# BMS_Carrier_-_Battery_Relay_Controls.net
KiCad netlist of a schematic drawn in Altium Designer
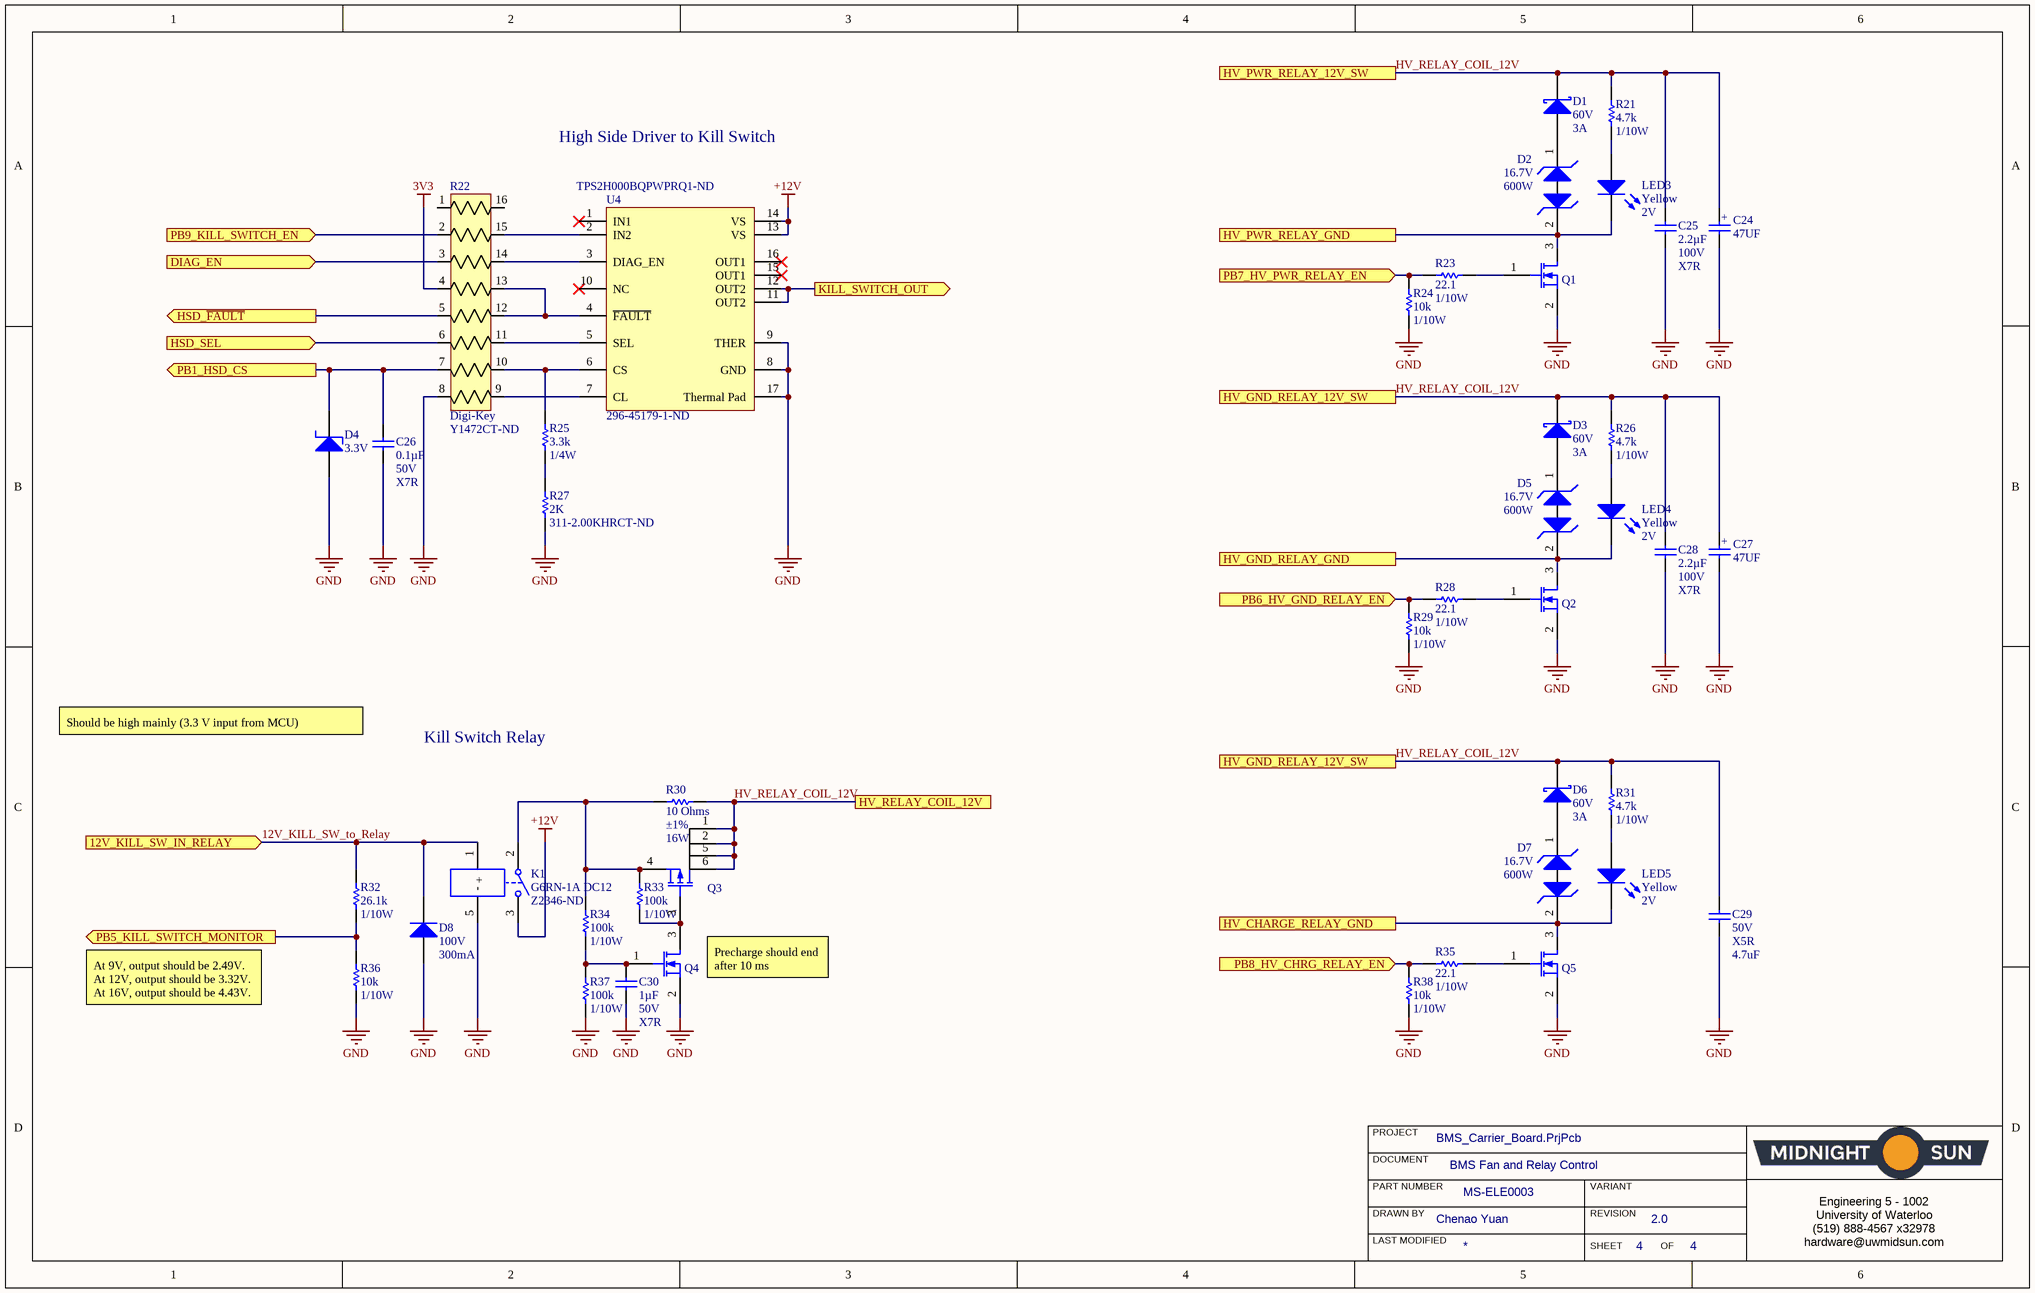
[diagram p0: BMS Carrier - Battery Relay Controls.SchDoc]

(export (version "E")
  (design (tool "Eeschema 10.0.6"))
  (components
    (comp (ref "C24")
      (value "47UF")
      (footprint "CAP ALUM 6.3MM RADIAL SMD")
      (description "47µF 35V Aluminum Electrolytic Capacitors Radial, Can - SMD 1000 Hrs @ 85°C")
      (fields (field (name "TOLERANCE") "20%") (field (name "MANUFACTURER") "Panasonic"))
      (libsource (lib "Schematic Diagrams") (part "CAP ALUM 47UF 20% 35V SMD"))
    )
    (comp (ref "C25")
      (value "CAP CER 2.2UF 100V ±20% X7R 1206")
      (footprint "CAP, 1206")
      (description "2.2µF ±20% 100V Ceramic Capacitor X7R 1206 (3216 Metric)")
      (fields
        (field (name "TOLERANCE") "±20%")
        (field (name "CAPACITANCE") "2.2µF")
        (field (name "VOLTAGE") "100V")
        (field (name "TEMPERATURE COEFFICIENT") "X7R")
      )
      (libsource (lib "Schematic Diagrams") (part "CAP CER 2.2UF 100V ±20% X7R 1206"))
    )
    (comp (ref "C26")
      (value "CAP CER 0.1UF 50V 10% X7R 0603")
      (footprint "CAP, 0603")
      (description "0.10µF ±10% 50V Ceramic Capacitor X7R 0603 (1608 Metric)")
      (fields
        (field (name "TOLERANCE") "±10%")
        (field (name "CAPACITANCE") "0.1µF")
        (field (name "VOLTAGE") "50V")
        (field (name "TEMPERATURE COEFFICIENT") "X7R")
      )
      (libsource (lib "Schematic Diagrams") (part "CAP CER 0.1UF 50V 10% X7R 0603"))
    )
    (comp (ref "C27")
      (value "47UF")
      (footprint "CAP ALUM 6.3MM RADIAL SMD")
      (description "47µF 35V Aluminum Electrolytic Capacitors Radial, Can - SMD 1000 Hrs @ 85°C")
      (fields (field (name "TOLERANCE") "20%") (field (name "MANUFACTURER") "Panasonic"))
      (libsource (lib "Schematic Diagrams") (part "CAP ALUM 47UF 20% 35V SMD"))
    )
    (comp (ref "C28")
      (value "CAP CER 2.2UF 100V ±20% X7R 1206")
      (footprint "CAP, 1206")
      (description "2.2µF ±20% 100V Ceramic Capacitor X7R 1206 (3216 Metric)")
      (fields
        (field (name "TOLERANCE") "±20%")
        (field (name "CAPACITANCE") "2.2µF")
        (field (name "VOLTAGE") "100V")
        (field (name "TEMPERATURE COEFFICIENT") "X7R")
      )
      (libsource (lib "Schematic Diagrams") (part "CAP CER 2.2UF 100V ±20% X7R 1206"))
    )
    (comp (ref "C29")
      (value "4.7uF")
      (footprint "CAP, 0805")
      (description "4.7µF ±20% 50V Ceramic Capacitor X5R 0805 (2012 Metric)")
      (fields
        (field (name "TOLERANCE") "±20%")
        (field (name "VOLTAGE - RATED") "50V")
        (field (name "TEMPERATURE COEFFICIENT") "X5R")
        (field (name "Comment") "CAP CER 4.7UF 50V 10% X5R 0805")
      )
      (libsource (lib "Schematic Diagrams") (part "CAP CER 4.7UF 50V 10% X5R 0805"))
    )
    (comp (ref "C30")
      (value "CAP CER 1UF 50V 10% X7R 0603")
      (footprint "CAP, 0603")
      (description "1µF ±10% 50V Ceramic Capacitor X7R 0603 (1608 Metric)")
      (fields
        (field (name "TOLERANCE") "±10%")
        (field (name "CAPACITANCE") "1µF")
        (field (name "VOLTAGE") "50V")
        (field (name "TEMPERATURE COEFFICIENT") "X7R")
      )
      (libsource (lib "Schematic Diagrams") (part "CAP CER 1UF 50V 10% X7R 0603"))
    )
    (comp (ref "D1")
      (value "DIODE SCHOTTKY 60V 3A SMA")
      (footprint "Diode, SMA")
      (description "Diode Schottky 60V 3A Surface Mount SMA")
      (fields
        (field (name "VOLTAGE - DC REVERSE (VR) (MAX)") "60V")
        (field (name "CURRENT - AVERAGE RECTIFIED (IO)") "3A")
      )
      (libsource (lib "Schematic Diagrams") (part "DIODE SCHOTTKY 60V 3A SMA"))
    )
    (comp (ref "D2")
      (value "DIODE TVS 15VWM 24.4VC DO-214AA (SMB)")
      (footprint "DO-214AA Diode")
      (description "TVS DIODE 15VWM 24.4VC SMB")
      (fields (field (name "VOLTAGE - BREAKDOWN (MIN)") "16.7V") (field (name "POWER - PEAK PULSE") "600W"))
      (libsource (lib "Schematic Diagrams") (part "DIODE TVS 15VWM 24.4VC DO-214AA (SMB)"))
    )
    (comp (ref "D3")
      (value "DIODE SCHOTTKY 60V 3A SMA")
      (footprint "Diode, SMA")
      (description "Diode Schottky 60V 3A Surface Mount SMA")
      (fields
        (field (name "VOLTAGE - DC REVERSE (VR) (MAX)") "60V")
        (field (name "CURRENT - AVERAGE RECTIFIED (IO)") "3A")
      )
      (libsource (lib "Schematic Diagrams") (part "DIODE SCHOTTKY 60V 3A SMA"))
    )
    (comp (ref "D4")
      (value "DIODE ZENER 3.3V 250mW")
      (footprint "Footprints:sot23")
      (description "Zener Diode 3.3V 250mW ±6.06% Surface Mount SSD3")
      (fields
        (field (name "TOLERANCE") "6.06%")
        (field (name "MANUFACTURER") "Rohm")
        (field (name "ZENER VOLTAGE") "3.3V")
      )
      (libsource (lib "Schematic Diagrams") (part "DIODE ZENER 3.3V 250mW"))
    )
    (comp (ref "D5")
      (value "DIODE TVS 15VWM 24.4VC DO-214AA (SMB)")
      (footprint "DO-214AA Diode")
      (description "TVS DIODE 15VWM 24.4VC SMB")
      (fields (field (name "VOLTAGE - BREAKDOWN (MIN)") "16.7V") (field (name "POWER - PEAK PULSE") "600W"))
      (libsource (lib "Schematic Diagrams") (part "DIODE TVS 15VWM 24.4VC DO-214AA (SMB)"))
    )
    (comp (ref "D6")
      (value "DIODE SCHOTTKY 60V 3A SMA")
      (footprint "Diode, SMA")
      (description "Diode Schottky 60V 3A Surface Mount SMA")
      (fields
        (field (name "VOLTAGE - DC REVERSE (VR) (MAX)") "60V")
        (field (name "CURRENT - AVERAGE RECTIFIED (IO)") "3A")
      )
      (libsource (lib "Schematic Diagrams") (part "DIODE SCHOTTKY 60V 3A SMA"))
    )
    (comp (ref "D7")
      (value "DIODE TVS 15VWM 24.4VC DO-214AA (SMB)")
      (footprint "DO-214AA Diode")
      (description "TVS DIODE 15VWM 24.4VC SMB")
      (fields (field (name "VOLTAGE - BREAKDOWN (MIN)") "16.7V") (field (name "POWER - PEAK PULSE") "600W"))
      (libsource (lib "Schematic Diagrams") (part "DIODE TVS 15VWM 24.4VC DO-214AA (SMB)"))
    )
    (comp (ref "D8")
      (value "DIODE GEN PURP 100V 300MA SOD123")
      (footprint "DIODE GEN PURP 100V 300MA SOD123")
      (description "Diode Standard 100V 300mA (DC) Surface Mount SOD-123")
      (fields
        (field (name "MANUFACTURER") "Diodes Zetex")
        (field (name "MANUFACTURER PART NUMBER") "1N4148WQ-7-F")
        (field (name "MAX REPETITIVE REVERSE VOLTAGE (VRRM)") "100V")
        (field (name "FORWARD CURRENT") "300mA")
      )
      (libsource (lib "Schematic Diagrams") (part "DIODE GEN PURP 100V 300MA SOD123"))
    )
    (comp (ref "K1")
      (value "G6RN-1A DC12")
      (footprint "Footprints:RELAY SPST 8A 12VDC")
      (description "Omron Relay SPST (1 Form A) Through Hole")
      (fields (field (name "SUPPLIER PART NUMBER 2") "Z2346-ND"))
      (libsource (lib "Schematic Diagrams") (part "RELAY SPST 12V 8A OMRON"))
    )
    (comp (ref "LED3")
      (value "LED YELLOW CLEAR 2.1V 0603")
      (footprint "LED_0603")
      (description "Yellow 590nm LED Indication - Discrete 2V 0603 (1608 Metric)")
      (fields
        (field (name "MANUFACTURER") "Wurth Electronics Inc.")
        (field (name "MANUFACTURER PART NUMBER") "150060YS75000")
        (field (name "COLOR") "Yellow")
        (field (name "VOLTAGE - FORWARD (VF) (TYP)") "2V")
      )
      (libsource (lib "Schematic Diagrams") (part "LED YELLOW CLEAR 2.1V 0603"))
    )
    (comp (ref "LED4")
      (value "LED YELLOW CLEAR 2.1V 0603")
      (footprint "LED_0603")
      (description "Yellow 590nm LED Indication - Discrete 2V 0603 (1608 Metric)")
      (fields
        (field (name "MANUFACTURER") "Wurth Electronics Inc.")
        (field (name "MANUFACTURER PART NUMBER") "150060YS75000")
        (field (name "COLOR") "Yellow")
        (field (name "VOLTAGE - FORWARD (VF) (TYP)") "2V")
      )
      (libsource (lib "Schematic Diagrams") (part "LED YELLOW CLEAR 2.1V 0603"))
    )
    (comp (ref "LED5")
      (value "LED YELLOW CLEAR 2.1V 0603")
      (footprint "LED_0603")
      (description "Yellow 590nm LED Indication - Discrete 2V 0603 (1608 Metric)")
      (fields
        (field (name "MANUFACTURER") "Wurth Electronics Inc.")
        (field (name "MANUFACTURER PART NUMBER") "150060YS75000")
        (field (name "COLOR") "Yellow")
        (field (name "VOLTAGE - FORWARD (VF) (TYP)") "2V")
      )
      (libsource (lib "Schematic Diagrams") (part "LED YELLOW CLEAR 2.1V 0603"))
    )
    (comp (ref "Q1")
      (value "MOSFET N-CH 30V 6.2A 0.9W SOT-23")
      (footprint "MOSFET N-CH 30V 6.2A 0.9W SOT-23")
      (description "N-Channel 30V 6.2A (Ta) 900mW (Ta) Surface Mount SOT-23")
      (fields (field (name "MANUFACTURER") "Diodes") (field (name "MANUFACTURER PART NUMBER") "DMN3023L-7"))
      (libsource (lib "Schematic Diagrams") (part "MOSFET N-CH 30V 6.2A 0.9W SOT-23"))
    )
    (comp (ref "Q2")
      (value "MOSFET N-CH 30V 6.2A 0.9W SOT-23")
      (footprint "MOSFET N-CH 30V 6.2A 0.9W SOT-23")
      (description "N-Channel 30V 6.2A (Ta) 900mW (Ta) Surface Mount SOT-23")
      (fields (field (name "MANUFACTURER") "Diodes") (field (name "MANUFACTURER PART NUMBER") "DMN3023L-7"))
      (libsource (lib "Schematic Diagrams") (part "MOSFET N-CH 30V 6.2A 0.9W SOT-23"))
    )
    (comp (ref "Q3")
      (value "MOSFET P-CH 30V 4A 1.6W SOT-23-6")
      (footprint "P-MOSFET")
      (description "P-Channel 30V 4A (Ta) 1.6W (Ta) Surface Mount SOT-23-6")
      (libsource (lib "Schematic Diagrams") (part "MOSFET P-CH 30V 4A 1.6W SOT-23-6"))
    )
    (comp (ref "Q4")
      (value "MOSFET N-CH 30V 6.2A 0.9W SOT-23")
      (footprint "MOSFET N-CH 30V 6.2A 0.9W SOT-23")
      (description "N-Channel 30V 6.2A (Ta) 900mW (Ta) Surface Mount SOT-23")
      (fields (field (name "MANUFACTURER") "Diodes") (field (name "MANUFACTURER PART NUMBER") "DMN3023L-7"))
      (libsource (lib "Schematic Diagrams") (part "MOSFET N-CH 30V 6.2A 0.9W SOT-23"))
    )
    (comp (ref "Q5")
      (value "MOSFET N-CH 30V 6.2A 0.9W SOT-23")
      (footprint "MOSFET N-CH 30V 6.2A 0.9W SOT-23")
      (description "N-Channel 30V 6.2A (Ta) 900mW (Ta) Surface Mount SOT-23")
      (fields (field (name "MANUFACTURER") "Diodes") (field (name "MANUFACTURER PART NUMBER") "DMN3023L-7"))
      (libsource (lib "Schematic Diagrams") (part "MOSFET N-CH 30V 6.2A 0.9W SOT-23"))
    )
    (comp (ref "R21")
      (value "RES 4.7K OHM 1% 1/10W 0603")
      (footprint "RES, 0603")
      (description "4.7k Ohm ±1% 0.1W, 1/10W Chip Resistor 0603 (1608 Metric) Moisture Resistant Thick Film")
      (fields
        (field (name "TOLERANCE") "±1%")
        (field (name "RESISTANCE (OHMS)") "4.7k")
        (field (name "POWER (WATTS)") "1/10W")
      )
      (libsource (lib "Schematic Diagrams") (part "RES 4.7K OHM 1% 1/10W 0603"))
    )
    (comp (ref "R22")
      (value "RES ARRAY 4K7 OHM 5% 8RES")
      (footprint "RES ARRAY, 8 POS 1506")
      (description "RES ARRAY SMD 4K7 5% 62.5mW 1506")
      (fields
        (field (name "MANUFACTURER") "Panasonic Electronic Components")
        (field (name "MANUFACTURER PART NUMBER") "EXB-2HV472JV")
        (field (name "SUPPLIER 1") "Digi-Key")
        (field (name "SUPPLIER PART NUMBER 1") "Y1472CT-ND")
      )
      (libsource (lib "Schematic Diagrams") (part "RES ARRAY 4.7K OHM 8 RES 1506"))
    )
    (comp (ref "R23")
      (value "RES 22.1 OHM 1% 1/10W 0603")
      (footprint "RES, 0603")
      (description "22.1 Ohm ±1% 0.1W, 1/10W Chip Resistor 0603 (1608 Metric) Moisture Resistant Thick Film")
      (fields
        (field (name "TOLERANCE") "±1%")
        (field (name "RESISTANCE") "22.1")
        (field (name "POWER") "1/10W")
      )
      (libsource (lib "Schematic Diagrams") (part "RES 22.1 OHM 1% 1/10W 0603"))
    )
    (comp (ref "R24")
      (value "RES 10K OHM 1% 1/10W 0603")
      (footprint "RES, 0603")
      (description "RES SMD 10K OHM 1% 1/10W 0603")
      (fields
        (field (name "TOLERANCE") "±1%")
        (field (name "RESISTANCE") "10k")
        (field (name "POWER") "1/10W")
      )
      (libsource (lib "Schematic Diagrams") (part "RES 10K OHM 1% 1/10W 0603"))
    )
    (comp (ref "R25")
      (value "RES 3.3K OHM 1% 1/4W 0603")
      (footprint "RES, 0603")
      (fields
        (field (name "TOLERANCE") "±1%")
        (field (name "RESISTANCE") "3.3k")
        (field (name "POWER") "1/4W")
      )
      (libsource (lib "Schematic Diagrams") (part "RES 3.3K OHM 1% 1/4W 0603"))
    )
    (comp (ref "R26")
      (value "RES 4.7K OHM 1% 1/10W 0603")
      (footprint "RES, 0603")
      (description "4.7k Ohm ±1% 0.1W, 1/10W Chip Resistor 0603 (1608 Metric) Moisture Resistant Thick Film")
      (fields
        (field (name "TOLERANCE") "±1%")
        (field (name "RESISTANCE (OHMS)") "4.7k")
        (field (name "POWER (WATTS)") "1/10W")
      )
      (libsource (lib "Schematic Diagrams") (part "RES 4.7K OHM 1% 1/10W 0603"))
    )
    (comp (ref "R27")
      (value "2K")
      (footprint "RES, 0603")
      (description "2k Ohm ±1% 0.1W, 1/10W Chip Resistor 0603 (1608 Metric) Moisture Resistant Thick Film")
      (fields
        (field (name "MANUFACTURER") "Yageo")
        (field (name "MANUFACTURER PART NUMBER") "RC0603FR-072KL")
        (field (name "SUPPLIER PART NUMBER 1") "311-2.00KHRCT-ND")
      )
      (libsource (lib "Schematic Diagrams") (part "RES 2K OHM 1% 1/10W 0603"))
    )
    (comp (ref "R28")
      (value "RES 22.1 OHM 1% 1/10W 0603")
      (footprint "RES, 0603")
      (description "22.1 Ohm ±1% 0.1W, 1/10W Chip Resistor 0603 (1608 Metric) Moisture Resistant Thick Film")
      (fields
        (field (name "TOLERANCE") "±1%")
        (field (name "RESISTANCE") "22.1")
        (field (name "POWER") "1/10W")
      )
      (libsource (lib "Schematic Diagrams") (part "RES 22.1 OHM 1% 1/10W 0603"))
    )
    (comp (ref "R29")
      (value "RES 10K OHM 1% 1/10W 0603")
      (footprint "RES, 0603")
      (description "RES SMD 10K OHM 1% 1/10W 0603")
      (fields
        (field (name "TOLERANCE") "±1%")
        (field (name "RESISTANCE") "10k")
        (field (name "POWER") "1/10W")
      )
      (libsource (lib "Schematic Diagrams") (part "RES 10K OHM 1% 1/10W 0603"))
    )
    (comp (ref "R30")
      (value "RES 10 OHM 1% 16W 2512")
      (footprint "RES2512")
      (description "10 Ohms ±1% 16W Chip Resistor 2512 (6432 Metric) Moisture Resistant Thin Film")
      (fields
        (field (name "RESISTANCE") "10 Ohms")
        (field (name "TOLERANCE") "±1%")
        (field (name "POWER") "16W")
      )
      (libsource (lib "Schematic Diagrams") (part "RES 10 OHM 1% 16W 2512"))
    )
    (comp (ref "R31")
      (value "RES 4.7K OHM 1% 1/10W 0603")
      (footprint "RES, 0603")
      (description "4.7k Ohm ±1% 0.1W, 1/10W Chip Resistor 0603 (1608 Metric) Moisture Resistant Thick Film")
      (fields
        (field (name "TOLERANCE") "±1%")
        (field (name "RESISTANCE (OHMS)") "4.7k")
        (field (name "POWER (WATTS)") "1/10W")
      )
      (libsource (lib "Schematic Diagrams") (part "RES 4.7K OHM 1% 1/10W 0603"))
    )
    (comp (ref "R32")
      (value "RES 26.1K OHM 1% 1/10W 0603")
      (footprint "RES, 0603")
      (description "RES SMD 26.1K OHM 1% 1/10W 0603")
      (fields
        (field (name "TOLERANCE") "±1%")
        (field (name "RESISTANCE") "26.1k")
        (field (name "POWER") "1/10W")
      )
      (libsource (lib "Schematic Diagrams") (part "RES 26.1K OHM 1% 1/10W 0603"))
    )
    (comp (ref "R33")
      (value "RES 100K OHM 5% 1/8W 0603")
      (footprint "RES, 0603")
      (description "RES SMD 100K OHM 5% 1/10W 0603")
      (fields
        (field (name "TOLERANCE") "±5%")
        (field (name "RESISTANCE") "100k")
        (field (name "POWER") "1/10W")
      )
      (libsource (lib "Schematic Diagrams") (part "RES 100K OHM 5% 1/8W 0603"))
    )
    (comp (ref "R34")
      (value "RES 100K OHM 5% 1/8W 0603")
      (footprint "RES, 0603")
      (description "RES SMD 100K OHM 5% 1/10W 0603")
      (fields
        (field (name "TOLERANCE") "±5%")
        (field (name "RESISTANCE") "100k")
        (field (name "POWER") "1/10W")
      )
      (libsource (lib "Schematic Diagrams") (part "RES 100K OHM 5% 1/8W 0603"))
    )
    (comp (ref "R35")
      (value "RES 22.1 OHM 1% 1/10W 0603")
      (footprint "RES, 0603")
      (description "22.1 Ohm ±1% 0.1W, 1/10W Chip Resistor 0603 (1608 Metric) Moisture Resistant Thick Film")
      (fields
        (field (name "TOLERANCE") "±1%")
        (field (name "RESISTANCE") "22.1")
        (field (name "POWER") "1/10W")
      )
      (libsource (lib "Schematic Diagrams") (part "RES 22.1 OHM 1% 1/10W 0603"))
    )
    (comp (ref "R36")
      (value "RES 10K OHM 1% 1/10W 0603")
      (footprint "RES, 0603")
      (description "RES SMD 10K OHM 1% 1/10W 0603")
      (fields
        (field (name "TOLERANCE") "±1%")
        (field (name "RESISTANCE") "10k")
        (field (name "POWER") "1/10W")
      )
      (libsource (lib "Schematic Diagrams") (part "RES 10K OHM 1% 1/10W 0603"))
    )
    (comp (ref "R37")
      (value "RES 100K OHM 5% 1/8W 0603")
      (footprint "RES, 0603")
      (description "RES SMD 100K OHM 5% 1/10W 0603")
      (fields
        (field (name "TOLERANCE") "±5%")
        (field (name "RESISTANCE") "100k")
        (field (name "POWER") "1/10W")
      )
      (libsource (lib "Schematic Diagrams") (part "RES 100K OHM 5% 1/8W 0603"))
    )
    (comp (ref "R38")
      (value "RES 10K OHM 1% 1/10W 0603")
      (footprint "RES, 0603")
      (description "RES SMD 10K OHM 1% 1/10W 0603")
      (fields
        (field (name "TOLERANCE") "±1%")
        (field (name "RESISTANCE") "10k")
        (field (name "POWER") "1/10W")
      )
      (libsource (lib "Schematic Diagrams") (part "RES 10K OHM 1% 1/10W 0603"))
    )
    (comp (ref "U4")
      (value "296-45179-1-ND")
      (footprint "IC HSD Dual-Channel TSOP65P640X120_HS-17N")
      (description "IC HSD Dual-Channel 40V 1KOhm")
      (fields
        (field (name "MANUFACTURER PART NUMBER") "TPS2H000BQPWPRQ1-ND")
        (field (name "SUPPLIER PART NUMBER 1") "TPS2H000BQPWPRQ1-ND")
      )
      (libsource (lib "Schematic Diagrams") (part "IC HSD Dual-Channel 40V 1KOhm"))
    )
  )
  (nets
    (net (code "1") (name "+12V") (class "Default")
      (node (ref "K1") (pin "3") (pinfunction "3_3") (pintype "passive"))
      (node (ref "U4") (pin "13") (pinfunction "VS_13") (pintype "passive"))
      (node (ref "U4") (pin "14") (pinfunction "VS_14") (pintype "passive"))
    )
    (net (code "2") (name "/12V_KILL_SW_to_Relay") (class "Default")
      (node (ref "D8") (pin "2") (pinfunction "K_2") (pintype "passive"))
      (node (ref "K1") (pin "1") (pinfunction "+_1") (pintype "passive"))
      (node (ref "R32") (pin "1") (pinfunction "1_1") (pintype "passive"))
    )
    (net (code "3") (name "/DIAG_EN") (class "Default")
      (node (ref "R22") (pin "3") (pinfunction "3_3") (pintype "passive"))
    )
    (net (code "4") (name "/HSD_SEL") (class "Default")
      (node (ref "R22") (pin "6") (pinfunction "6_6") (pintype "passive"))
    )
    (net (code "5") (name "/HSD_~{FAULT}") (class "Default")
      (node (ref "R22") (pin "5") (pinfunction "5_5") (pintype "passive"))
    )
    (net (code "6") (name "/HV_CHARGE_RELAY_GND") (class "Default")
      (node (ref "D7") (pin "2") (pinfunction "Cathode2_2") (pintype "passive"))
      (node (ref "LED5") (pin "2") (pinfunction "K_2") (pintype "passive"))
      (node (ref "Q5") (pin "3") (pinfunction "D_3") (pintype "passive"))
    )
    (net (code "7") (name "/HV_GND_RELAY_GND") (class "Default")
      (node (ref "D5") (pin "2") (pinfunction "Cathode2_2") (pintype "passive"))
      (node (ref "LED4") (pin "2") (pinfunction "K_2") (pintype "passive"))
      (node (ref "Q2") (pin "3") (pinfunction "D_3") (pintype "passive"))
    )
    (net (code "8") (name "/HV_PWR_RELAY_GND") (class "Default")
      (node (ref "D2") (pin "2") (pinfunction "Cathode2_2") (pintype "passive"))
      (node (ref "LED3") (pin "2") (pinfunction "K_2") (pintype "passive"))
      (node (ref "Q1") (pin "3") (pinfunction "D_3") (pintype "passive"))
    )
    (net (code "9") (name "/HV_RELAY_COIL_12V") (class "Default")
      (node (ref "C24") (pin "1") (pinfunction "1_1") (pintype "passive"))
      (node (ref "C25") (pin "1") (pinfunction "1_1") (pintype "passive"))
      (node (ref "C27") (pin "1") (pinfunction "1_1") (pintype "passive"))
      (node (ref "C28") (pin "1") (pinfunction "1_1") (pintype "passive"))
      (node (ref "C29") (pin "1") (pinfunction "1_1") (pintype "passive"))
      (node (ref "D1") (pin "2") (pinfunction "2_2") (pintype "passive"))
      (node (ref "D3") (pin "2") (pinfunction "2_2") (pintype "passive"))
      (node (ref "D6") (pin "2") (pinfunction "2_2") (pintype "passive"))
      (node (ref "Q3") (pin "1") (pinfunction "D_1") (pintype "passive"))
      (node (ref "Q3") (pin "2") (pinfunction "D_2") (pintype "passive"))
      (node (ref "Q3") (pin "5") (pinfunction "D_5") (pintype "passive"))
      (node (ref "Q3") (pin "6") (pinfunction "D_6") (pintype "passive"))
      (node (ref "R21") (pin "1") (pinfunction "1_1") (pintype "passive"))
      (node (ref "R26") (pin "1") (pinfunction "1_1") (pintype "passive"))
      (node (ref "R30") (pin "2") (pinfunction "2_2") (pintype "passive"))
      (node (ref "R31") (pin "1") (pinfunction "1_1") (pintype "passive"))
    )
    (net (code "10") (name "/KILL_SWITCH_OUT") (class "Default")
      (node (ref "U4") (pin "11") (pinfunction "OUT2_11") (pintype "passive"))
      (node (ref "U4") (pin "12") (pinfunction "OUT2_12") (pintype "passive"))
    )
    (net (code "11") (name "/PB1_HSD_CS") (class "Default")
      (node (ref "C26") (pin "1") (pinfunction "1_1") (pintype "passive"))
      (node (ref "D4") (pin "1") (pinfunction "K_1") (pintype "passive"))
      (node (ref "R22") (pin "7") (pinfunction "7_7") (pintype "passive"))
    )
    (net (code "12") (name "/PB5_KILL_SWITCH_MONITOR") (class "Default")
      (node (ref "R32") (pin "2") (pinfunction "2_2") (pintype "passive"))
      (node (ref "R36") (pin "1") (pinfunction "1_1") (pintype "passive"))
    )
    (net (code "13") (name "/PB6_HV_GND_RELAY_EN") (class "Default")
      (node (ref "R28") (pin "1") (pinfunction "1_1") (pintype "passive"))
      (node (ref "R29") (pin "1") (pinfunction "1_1") (pintype "passive"))
    )
    (net (code "14") (name "/PB7_HV_PWR_RELAY_EN") (class "Default")
      (node (ref "R23") (pin "1") (pinfunction "1_1") (pintype "passive"))
      (node (ref "R24") (pin "1") (pinfunction "1_1") (pintype "passive"))
    )
    (net (code "15") (name "/PB8_HV_CHRG_RELAY_EN") (class "Default")
      (node (ref "R35") (pin "1") (pinfunction "1_1") (pintype "passive"))
      (node (ref "R38") (pin "1") (pinfunction "1_1") (pintype "passive"))
    )
    (net (code "16") (name "/PB9_KILL_SWITCH_EN") (class "Default")
      (node (ref "R22") (pin "2") (pinfunction "2_2") (pintype "passive"))
    )
    (net (code "17") (name "3V3") (class "Default")
      (node (ref "R22") (pin "4") (pinfunction "4_4") (pintype "passive"))
    )
    (net (code "18") (name "GND") (class "Default")
      (node (ref "C24") (pin "2") (pinfunction "2_2") (pintype "passive"))
      (node (ref "C25") (pin "2") (pinfunction "2_2") (pintype "passive"))
      (node (ref "C26") (pin "2") (pinfunction "2_2") (pintype "passive"))
      (node (ref "C27") (pin "2") (pinfunction "2_2") (pintype "passive"))
      (node (ref "C28") (pin "2") (pinfunction "2_2") (pintype "passive"))
      (node (ref "C29") (pin "2") (pinfunction "2_2") (pintype "passive"))
      (node (ref "C30") (pin "2") (pinfunction "2_2") (pintype "passive"))
      (node (ref "D4") (pin "3") (pinfunction "A_3") (pintype "passive"))
      (node (ref "D8") (pin "1") (pinfunction "A_1") (pintype "passive"))
      (node (ref "K1") (pin "5") (pinfunction "-_5") (pintype "passive"))
      (node (ref "Q1") (pin "2") (pinfunction "S_2") (pintype "passive"))
      (node (ref "Q2") (pin "2") (pinfunction "S_2") (pintype "passive"))
      (node (ref "Q4") (pin "2") (pinfunction "S_2") (pintype "passive"))
      (node (ref "Q5") (pin "2") (pinfunction "S_2") (pintype "passive"))
      (node (ref "R22") (pin "8") (pinfunction "8_8") (pintype "passive"))
      (node (ref "R24") (pin "2") (pinfunction "2_2") (pintype "passive"))
      (node (ref "R27") (pin "2") (pinfunction "2_2") (pintype "passive"))
      (node (ref "R29") (pin "2") (pinfunction "2_2") (pintype "passive"))
      (node (ref "R36") (pin "2") (pinfunction "2_2") (pintype "passive"))
      (node (ref "R37") (pin "2") (pinfunction "2_2") (pintype "passive"))
      (node (ref "R38") (pin "2") (pinfunction "2_2") (pintype "passive"))
      (node (ref "U4") (pin "17") (pinfunction "Thermal_Pad_17") (pintype "passive"))
      (node (ref "U4") (pin "8") (pinfunction "GND_8") (pintype "passive"))
      (node (ref "U4") (pin "9") (pinfunction "THER_9") (pintype "passive"))
    )
    (net (code "19") (name "Net-(D2-Cathode1)") (class "Default")
      (node (ref "D1") (pin "1") (pinfunction "1_1") (pintype "passive"))
      (node (ref "D2") (pin "1") (pinfunction "Cathode1_1") (pintype "passive"))
    )
    (net (code "20") (name "Net-(D5-Cathode1)") (class "Default")
      (node (ref "D3") (pin "1") (pinfunction "1_1") (pintype "passive"))
      (node (ref "D5") (pin "1") (pinfunction "Cathode1_1") (pintype "passive"))
    )
    (net (code "21") (name "Net-(D7-Cathode1)") (class "Default")
      (node (ref "D6") (pin "1") (pinfunction "1_1") (pintype "passive"))
      (node (ref "D7") (pin "1") (pinfunction "Cathode1_1") (pintype "passive"))
    )
    (net (code "22") (name "Net-(LED3-A)") (class "Default")
      (node (ref "LED3") (pin "1") (pinfunction "A_1") (pintype "passive"))
      (node (ref "R21") (pin "2") (pinfunction "2_2") (pintype "passive"))
    )
    (net (code "23") (name "Net-(LED4-A)") (class "Default")
      (node (ref "LED4") (pin "1") (pinfunction "A_1") (pintype "passive"))
      (node (ref "R26") (pin "2") (pinfunction "2_2") (pintype "passive"))
    )
    (net (code "24") (name "Net-(LED5-A)") (class "Default")
      (node (ref "LED5") (pin "1") (pinfunction "A_1") (pintype "passive"))
      (node (ref "R31") (pin "2") (pinfunction "2_2") (pintype "passive"))
    )
    (net (code "25") (name "Net-(Q1-G)") (class "Default")
      (node (ref "Q1") (pin "1") (pinfunction "G_1") (pintype "passive"))
      (node (ref "R23") (pin "2") (pinfunction "2_2") (pintype "passive"))
    )
    (net (code "26") (name "Net-(Q2-G)") (class "Default")
      (node (ref "Q2") (pin "1") (pinfunction "G_1") (pintype "passive"))
      (node (ref "R28") (pin "2") (pinfunction "2_2") (pintype "passive"))
    )
    (net (code "27") (name "Net-(Q3-G)") (class "Default")
      (node (ref "Q3") (pin "3") (pinfunction "G_3") (pintype "passive"))
      (node (ref "Q4") (pin "3") (pinfunction "D_3") (pintype "passive"))
      (node (ref "R33") (pin "1") (pinfunction "1_1") (pintype "passive"))
    )
    (net (code "28") (name "Net-(Q3-S)") (class "Default")
      (node (ref "K1") (pin "2") (pinfunction "2_2") (pintype "passive"))
      (node (ref "Q3") (pin "4") (pinfunction "S_4") (pintype "passive"))
      (node (ref "R30") (pin "1") (pinfunction "1_1") (pintype "passive"))
      (node (ref "R33") (pin "2") (pinfunction "2_2") (pintype "passive"))
      (node (ref "R34") (pin "1") (pinfunction "1_1") (pintype "passive"))
    )
    (net (code "29") (name "Net-(Q4-G)") (class "Default")
      (node (ref "C30") (pin "1") (pinfunction "1_1") (pintype "passive"))
      (node (ref "Q4") (pin "1") (pinfunction "G_1") (pintype "passive"))
      (node (ref "R34") (pin "2") (pinfunction "2_2") (pintype "passive"))
      (node (ref "R37") (pin "1") (pinfunction "1_1") (pintype "passive"))
    )
    (net (code "30") (name "Net-(Q5-G)") (class "Default")
      (node (ref "Q5") (pin "1") (pinfunction "G_1") (pintype "passive"))
      (node (ref "R35") (pin "2") (pinfunction "2_2") (pintype "passive"))
    )
    (net (code "31") (name "Net-(R25-Pad2)") (class "Default")
      (node (ref "R25") (pin "2") (pinfunction "2_2") (pintype "passive"))
      (node (ref "R27") (pin "1") (pinfunction "1_1") (pintype "passive"))
    )
    (net (code "32") (name "Net-(U4-CL)") (class "Default")
      (node (ref "R22") (pin "9") (pinfunction "9_9") (pintype "passive"))
      (node (ref "U4") (pin "7") (pinfunction "CL_7") (pintype "passive"))
    )
    (net (code "33") (name "Net-(U4-CS)") (class "Default")
      (node (ref "R22") (pin "10") (pinfunction "10_10") (pintype "passive"))
      (node (ref "R25") (pin "1") (pinfunction "1_1") (pintype "passive"))
      (node (ref "U4") (pin "6") (pinfunction "CS_6") (pintype "passive"))
    )
    (net (code "34") (name "Net-(U4-DIAG_EN)") (class "Default")
      (node (ref "R22") (pin "14") (pinfunction "14_14") (pintype "passive"))
      (node (ref "U4") (pin "3") (pinfunction "DIAG_EN_3") (pintype "passive"))
    )
    (net (code "35") (name "Net-(U4-IN2)") (class "Default")
      (node (ref "R22") (pin "15") (pinfunction "15_15") (pintype "passive"))
      (node (ref "U4") (pin "2") (pinfunction "IN2_2") (pintype "passive"))
    )
    (net (code "36") (name "Net-(U4-SEL)") (class "Default")
      (node (ref "R22") (pin "11") (pinfunction "11_11") (pintype "passive"))
      (node (ref "U4") (pin "5") (pinfunction "SEL_5") (pintype "passive"))
    )
    (net (code "37") (name "Net-(U4-~{FAULT})") (class "Default")
      (node (ref "R22") (pin "12") (pinfunction "12_12") (pintype "passive"))
      (node (ref "R22") (pin "13") (pinfunction "13_13") (pintype "passive"))
      (node (ref "U4") (pin "4") (pinfunction "~{FAULT}_4") (pintype "passive"))
    )
    (net (code "38") (name "unconnected-(D4-NC-Pad2)") (class "Default")
      (node (ref "D4") (pin "2") (pinfunction "NC_2") (pintype "passive"))
    )
    (net (code "39") (name "unconnected-(R22-Pad1)") (class "Default")
      (node (ref "R22") (pin "1") (pinfunction "1_1") (pintype "passive"))
    )
    (net (code "40") (name "unconnected-(R22-Pad16)") (class "Default")
      (node (ref "R22") (pin "16") (pinfunction "16_16") (pintype "passive"))
    )
    (net (code "41") (name "unconnected-(U4-IN1-Pad1)") (class "Default")
      (node (ref "U4") (pin "1") (pinfunction "IN1_1") (pintype "passive+no_connect"))
    )
    (net (code "42") (name "unconnected-(U4-NC-Pad10)") (class "Default")
      (node (ref "U4") (pin "10") (pinfunction "NC_10") (pintype "passive+no_connect"))
    )
    (net (code "43") (name "unconnected-(U4-OUT1-Pad15)") (class "Default")
      (node (ref "U4") (pin "15") (pinfunction "OUT1_15") (pintype "passive+no_connect"))
    )
    (net (code "44") (name "unconnected-(U4-OUT1-Pad16)") (class "Default")
      (node (ref "U4") (pin "16") (pinfunction "OUT1_16") (pintype "passive+no_connect"))
    )
  )
)
